# 1_Cube_Sensor.net
KiCad netlist of a schematic drawn in Altium Designer
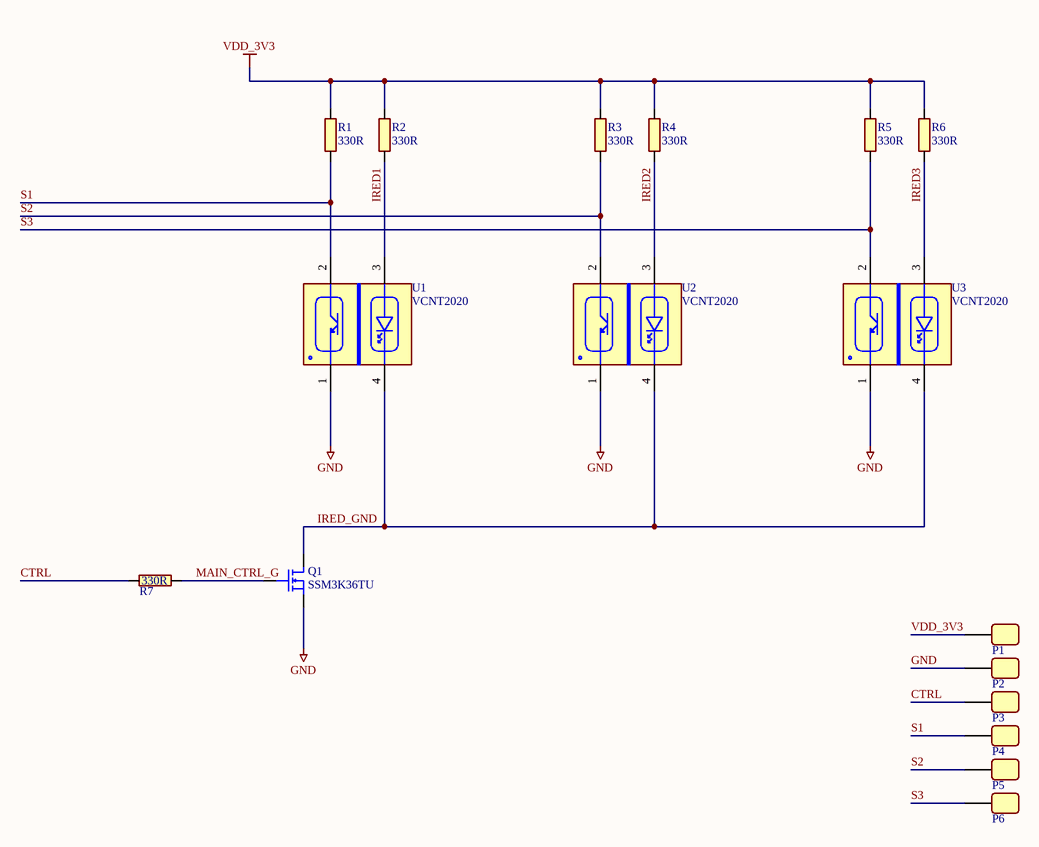
[diagram p0: [1] Cube_Sensor.SchDoc]

(export (version "E")
  (design (tool "Eeschema 10.0.6"))
  (components
    (comp (ref "P1")
      (value "PAD_4")
      (footprint "PAD_B2B")
      (description "a Pad for board to board connection")
      (libsource (lib "Cube Library") (part "PAD_4"))
    )
    (comp (ref "P2")
      (value "PAD_4")
      (footprint "PAD_B2B")
      (description "a Pad for board to board connection")
      (libsource (lib "Cube Library") (part "PAD_4"))
    )
    (comp (ref "P3")
      (value "PAD_4")
      (footprint "PAD_B2B")
      (description "a Pad for board to board connection")
      (libsource (lib "Cube Library") (part "PAD_4"))
    )
    (comp (ref "P4")
      (value "PAD_4")
      (footprint "PAD_B2B")
      (description "a Pad for board to board connection")
      (libsource (lib "Cube Library") (part "PAD_4"))
    )
    (comp (ref "P5")
      (value "PAD_4")
      (footprint "PAD_B2B")
      (description "a Pad for board to board connection")
      (libsource (lib "Cube Library") (part "PAD_4"))
    )
    (comp (ref "P6")
      (value "PAD_4")
      (footprint "PAD_B2B")
      (description "a Pad for board to board connection")
      (libsource (lib "Cube Library") (part "PAD_4"))
    )
    (comp (ref "Q1")
      (value "SSM3K36TU")
      (footprint "SSM3K36TU")
      (description "N-Channel 20V 500mA (Ta) 800mW (Ta) Surface Mount UFM")
      (fields (field (name "MANUFACTURER") "Toshiba Semiconductor and Storage"))
      (libsource (lib "Cube Library") (part "SSM3K36TU"))
    )
    (comp (ref "R1")
      (value "330R")
      (footprint "RESC0402X04N")
      (description "RES SMD 330R OHM 1% 1/16W 0402")
      (fields
        (field (name "MANUFACTURER") "YAGEO")
        (field (name "MANUFACTURER PART NUMBER") "RC0402FR-07330RL")
        (field (name "RESISTANCE") "330R")
      )
      (libsource (lib "Cube Library") (part "RES 330R"))
    )
    (comp (ref "R2")
      (value "330R")
      (footprint "RESC0402X04N")
      (description "RES SMD 330R OHM 1% 1/16W 0402")
      (fields
        (field (name "MANUFACTURER") "YAGEO")
        (field (name "MANUFACTURER PART NUMBER") "RC0402FR-07330RL")
        (field (name "RESISTANCE") "330R")
      )
      (libsource (lib "Cube Library") (part "RES 330R"))
    )
    (comp (ref "R3")
      (value "330R")
      (footprint "RESC0402X04N")
      (description "RES SMD 330R OHM 1% 1/16W 0402")
      (fields
        (field (name "MANUFACTURER") "YAGEO")
        (field (name "MANUFACTURER PART NUMBER") "RC0402FR-07330RL")
        (field (name "RESISTANCE") "330R")
      )
      (libsource (lib "Cube Library") (part "RES 330R"))
    )
    (comp (ref "R4")
      (value "330R")
      (footprint "RESC0402X04N")
      (description "RES SMD 330R OHM 1% 1/16W 0402")
      (fields
        (field (name "MANUFACTURER") "YAGEO")
        (field (name "MANUFACTURER PART NUMBER") "RC0402FR-07330RL")
        (field (name "RESISTANCE") "330R")
      )
      (libsource (lib "Cube Library") (part "RES 330R"))
    )
    (comp (ref "R5")
      (value "330R")
      (footprint "RESC0402X04N")
      (description "RES SMD 330R OHM 1% 1/16W 0402")
      (fields
        (field (name "MANUFACTURER") "YAGEO")
        (field (name "MANUFACTURER PART NUMBER") "RC0402FR-07330RL")
        (field (name "RESISTANCE") "330R")
      )
      (libsource (lib "Cube Library") (part "RES 330R"))
    )
    (comp (ref "R6")
      (value "330R")
      (footprint "RESC0402X04N")
      (description "RES SMD 330R OHM 1% 1/16W 0402")
      (fields
        (field (name "MANUFACTURER") "YAGEO")
        (field (name "MANUFACTURER PART NUMBER") "RC0402FR-07330RL")
        (field (name "RESISTANCE") "330R")
      )
      (libsource (lib "Cube Library") (part "RES 330R"))
    )
    (comp (ref "R7")
      (value "330R")
      (footprint "RESC0402X04N")
      (description "RES SMD 330R OHM 1% 1/16W 0402")
      (fields
        (field (name "MANUFACTURER") "YAGEO")
        (field (name "MANUFACTURER PART NUMBER") "RC0402FR-07330RL")
        (field (name "RESISTANCE") "330R")
      )
      (libsource (lib "") (part "RES 330R_1"))
    )
    (comp (ref "U1")
      (value "VCNT2020")
      (footprint "VCNT2020")
      (description "REFLECTIVE SENSOR WITH PTR OUTPU")
      (fields (field (name "MANUFACTURER") "Vishay Semiconductor Opto Division"))
      (libsource (lib "Cube Library") (part "VCNT2020"))
    )
    (comp (ref "U2")
      (value "VCNT2020")
      (footprint "VCNT2020")
      (description "REFLECTIVE SENSOR WITH PTR OUTPU")
      (fields (field (name "MANUFACTURER") "Vishay Semiconductor Opto Division"))
      (libsource (lib "Cube Library") (part "VCNT2020"))
    )
    (comp (ref "U3")
      (value "VCNT2020")
      (footprint "VCNT2020")
      (description "REFLECTIVE SENSOR WITH PTR OUTPU")
      (fields (field (name "MANUFACTURER") "Vishay Semiconductor Opto Division"))
      (libsource (lib "Cube Library") (part "VCNT2020"))
    )
  )
  (nets
    (net (code "1") (name "/CTRL") (class "Default")
      (node (ref "P3") (pin "1") (pinfunction "1_1") (pintype "passive"))
      (node (ref "R7") (pin "2") (pinfunction "2_2") (pintype "passive"))
    )
    (net (code "2") (name "/IRED1") (class "Default")
      (node (ref "R2") (pin "1") (pinfunction "1_1") (pintype "passive"))
      (node (ref "U1") (pin "3") (pinfunction "3_3") (pintype "passive"))
    )
    (net (code "3") (name "/IRED2") (class "Default")
      (node (ref "R4") (pin "1") (pinfunction "1_1") (pintype "passive"))
      (node (ref "U2") (pin "3") (pinfunction "3_3") (pintype "passive"))
    )
    (net (code "4") (name "/IRED3") (class "Default")
      (node (ref "R6") (pin "1") (pinfunction "1_1") (pintype "passive"))
      (node (ref "U3") (pin "3") (pinfunction "3_3") (pintype "passive"))
    )
    (net (code "5") (name "/IRED_GND") (class "Default")
      (node (ref "Q1") (pin "3") (pinfunction "3_3") (pintype "passive"))
      (node (ref "U1") (pin "4") (pinfunction "4_4") (pintype "passive"))
      (node (ref "U2") (pin "4") (pinfunction "4_4") (pintype "passive"))
      (node (ref "U3") (pin "4") (pinfunction "4_4") (pintype "passive"))
    )
    (net (code "6") (name "/MAIN_CTRL_G") (class "Default")
      (node (ref "Q1") (pin "1") (pinfunction "1_1") (pintype "passive"))
      (node (ref "R7") (pin "1") (pinfunction "1_1") (pintype "passive"))
    )
    (net (code "7") (name "/S1") (class "Default")
      (node (ref "P4") (pin "1") (pinfunction "1_1") (pintype "passive"))
      (node (ref "R1") (pin "1") (pinfunction "1_1") (pintype "passive"))
      (node (ref "U1") (pin "2") (pinfunction "2_2") (pintype "passive"))
    )
    (net (code "8") (name "/S2") (class "Default")
      (node (ref "P5") (pin "1") (pinfunction "1_1") (pintype "passive"))
      (node (ref "R3") (pin "1") (pinfunction "1_1") (pintype "passive"))
      (node (ref "U2") (pin "2") (pinfunction "2_2") (pintype "passive"))
    )
    (net (code "9") (name "/S3") (class "Default")
      (node (ref "P6") (pin "1") (pinfunction "1_1") (pintype "passive"))
      (node (ref "R5") (pin "1") (pinfunction "1_1") (pintype "passive"))
      (node (ref "U3") (pin "2") (pinfunction "2_2") (pintype "passive"))
    )
    (net (code "10") (name "GND") (class "Default")
      (node (ref "P2") (pin "1") (pinfunction "1_1") (pintype "passive"))
      (node (ref "Q1") (pin "2") (pinfunction "2_2") (pintype "passive"))
      (node (ref "U1") (pin "1") (pinfunction "1_1") (pintype "passive"))
      (node (ref "U2") (pin "1") (pinfunction "1_1") (pintype "passive"))
      (node (ref "U3") (pin "1") (pinfunction "1_1") (pintype "passive"))
    )
    (net (code "11") (name "VDD_3V3") (class "Default")
      (node (ref "P1") (pin "1") (pinfunction "1_1") (pintype "passive"))
      (node (ref "R1") (pin "2") (pinfunction "2_2") (pintype "passive"))
      (node (ref "R2") (pin "2") (pinfunction "2_2") (pintype "passive"))
      (node (ref "R3") (pin "2") (pinfunction "2_2") (pintype "passive"))
      (node (ref "R4") (pin "2") (pinfunction "2_2") (pintype "passive"))
      (node (ref "R5") (pin "2") (pinfunction "2_2") (pintype "passive"))
      (node (ref "R6") (pin "2") (pinfunction "2_2") (pintype "passive"))
    )
  )
)
